# sphericon_v3.net
KiCad netlist of a schematic drawn in EAGLE
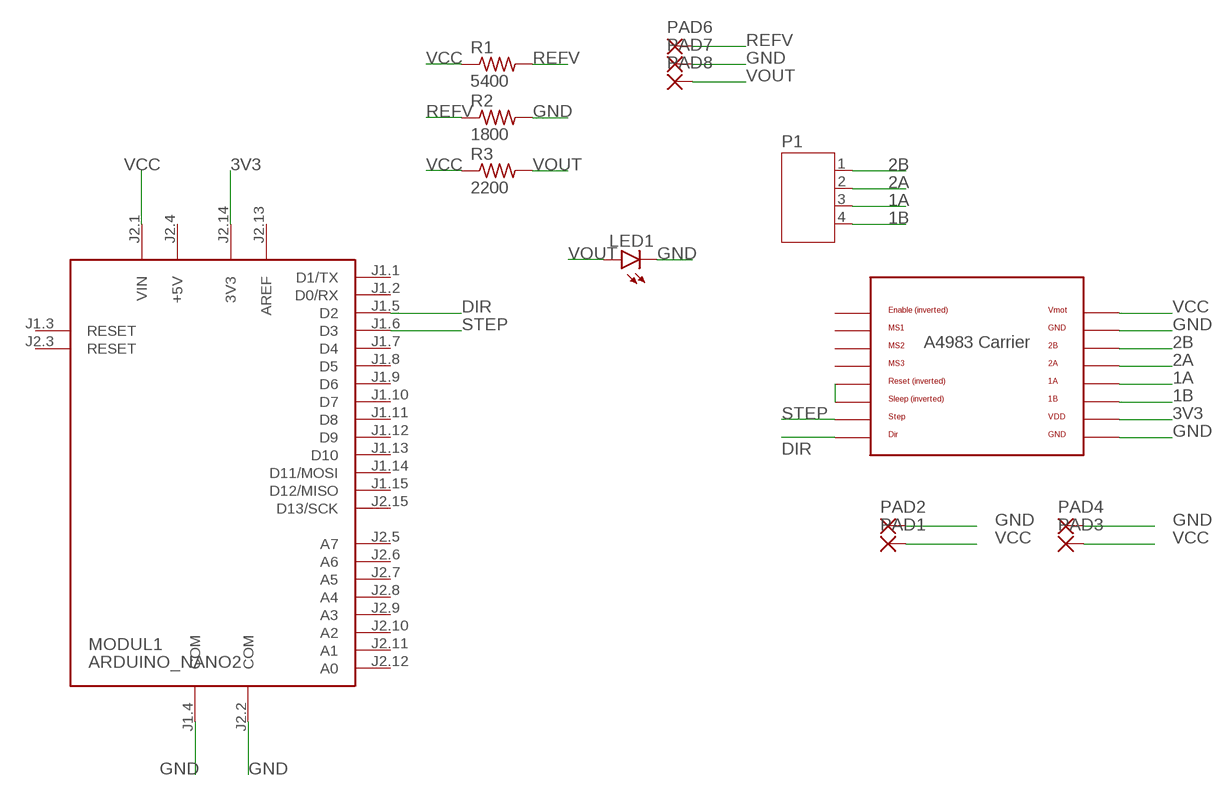
[diagram p0: schematic, sheet 1]

(export (version "E")
  (design (tool "Eeschema 10.0.6"))
  (components
    (comp (ref "LED1")
      (value "LED3MM")
      (footprint "eagle-import:LED3MM")
      (libsource (lib "eagle-import") (part "LED3MM"))
    )
    (comp (ref "MODUL1")
      (value "ARDUINO_NANO2")
      (footprint "eagle-import:ARDUINO_NANO2")
      (libsource (lib "eagle-import") (part "ARDUINO_NANO2"))
    )
    (comp (ref "P1")
      (value "JST-PH4")
      (footprint "eagle-import:JST-PH4")
      (libsource (lib "eagle-import") (part "JST-PH4"))
    )
    (comp (ref "PAD1")
      (value "1,6/0,8")
      (footprint "eagle-import:1,6_0,8")
      (libsource (lib "eagle-import") (part "1,6/0,8"))
    )
    (comp (ref "PAD2")
      (value "1,6/0,8")
      (footprint "eagle-import:1,6_0,8")
      (libsource (lib "eagle-import") (part "1,6/0,8"))
    )
    (comp (ref "PAD3")
      (value "1,6/0,8")
      (footprint "eagle-import:1,6_0,8")
      (libsource (lib "eagle-import") (part "1,6/0,8"))
    )
    (comp (ref "PAD4")
      (value "1,6/0,8")
      (footprint "eagle-import:1,6_0,8")
      (libsource (lib "eagle-import") (part "1,6/0,8"))
    )
    (comp (ref "PAD6")
      (value "1,6/0,8")
      (footprint "eagle-import:1,6_0,8")
      (libsource (lib "eagle-import") (part "1,6/0,8"))
    )
    (comp (ref "PAD7")
      (value "1,6/0,8")
      (footprint "eagle-import:1,6_0,8")
      (libsource (lib "eagle-import") (part "1,6/0,8"))
    )
    (comp (ref "PAD8")
      (value "1,6/0,8")
      (footprint "eagle-import:1,6_0,8")
      (libsource (lib "eagle-import") (part "1,6/0,8"))
    )
    (comp (ref "R1")
      (value "5400")
      (footprint "eagle-import:0204V")
      (libsource (lib "eagle-import") (part "R-US_0204/2V"))
    )
    (comp (ref "R2")
      (value "1800")
      (footprint "eagle-import:0204V")
      (libsource (lib "eagle-import") (part "R-US_0204/2V"))
    )
    (comp (ref "R3")
      (value "2200")
      (footprint "eagle-import:0204V")
      (libsource (lib "eagle-import") (part "R-US_0204/2V"))
    )
    (comp (ref "U$6")
      (value "POLOLU_A4983CARRIER")
      (footprint "eagle-import:A4983CARRIER")
      (libsource (lib "eagle-import") (part "POLOLU_A4983CARRIER"))
    )
  )
  (nets
    (net (code "1") (name "+5V") (class "Default")
      (node (ref "MODUL1") (pin "J2.4") (pinfunction "+5V_J2.4") (pintype "power_in"))
    )
    (net (code "2") (name "1A") (class "Default")
      (node (ref "P1") (pin "3") (pinfunction "3_3") (pintype "passive"))
      (node (ref "U$6") (pin "1A") (pinfunction "1A_1A") (pintype "output"))
    )
    (net (code "3") (name "1B") (class "Default")
      (node (ref "P1") (pin "4") (pinfunction "4_4") (pintype "passive"))
      (node (ref "U$6") (pin "1B") (pinfunction "1B_1B") (pintype "output"))
    )
    (net (code "4") (name "2A") (class "Default")
      (node (ref "P1") (pin "2") (pinfunction "2_2") (pintype "passive"))
      (node (ref "U$6") (pin "2A") (pinfunction "2A_2A") (pintype "output"))
    )
    (net (code "5") (name "2B") (class "Default")
      (node (ref "P1") (pin "1") (pinfunction "1_1") (pintype "passive"))
      (node (ref "U$6") (pin "2B") (pinfunction "2B_2B") (pintype "output"))
    )
    (net (code "6") (name "3V3") (class "Default")
      (node (ref "MODUL1") (pin "J2.14") (pinfunction "3V3_J2.14") (pintype "power_in"))
      (node (ref "U$6") (pin "VDD") (pinfunction "VDD_VDD") (pintype "power_in"))
    )
    (net (code "7") (name "AREF") (class "Default")
      (node (ref "MODUL1") (pin "J2.13") (pinfunction "AREF_J2.13") (pintype "power_in"))
    )
    (net (code "8") (name "DIR") (class "Default")
      (node (ref "MODUL1") (pin "J1.5") (pinfunction "D2_J1.5") (pintype "bidirectional"))
      (node (ref "U$6") (pin "DIR") (pinfunction "DIR_DIR") (pintype "input"))
    )
    (net (code "9") (name "GND") (class "Default")
      (node (ref "LED1") (pin "K") (pinfunction "C_K") (pintype "passive"))
      (node (ref "MODUL1") (pin "J1.4") (pinfunction "COM_J1.4") (pintype "power_in"))
      (node (ref "MODUL1") (pin "J2.2") (pinfunction "COM_J2.2") (pintype "power_in"))
      (node (ref "PAD2") (pin "1") (pinfunction "P_1") (pintype "passive"))
      (node (ref "PAD4") (pin "1") (pinfunction "P_1") (pintype "passive"))
      (node (ref "PAD7") (pin "1") (pinfunction "P_1") (pintype "passive"))
      (node (ref "R2") (pin "2") (pinfunction "2_2") (pintype "passive"))
      (node (ref "U$6") (pin "GND") (pinfunction "GND_GND") (pintype "power_in"))
      (node (ref "U$6") (pin "GND@0") (pinfunction "GND_GND@0") (pintype "power_in"))
    )
    (net (code "10") (name "Net-(U$6-SLEEP)") (class "Default")
      (node (ref "U$6") (pin "RST") (pinfunction "RST_RST") (pintype "input"))
      (node (ref "U$6") (pin "SLP") (pinfunction "SLEEP_SLP") (pintype "input"))
    )
    (net (code "11") (name "REFV") (class "Default")
      (node (ref "PAD6") (pin "1") (pinfunction "P_1") (pintype "passive"))
      (node (ref "R1") (pin "2") (pinfunction "2_2") (pintype "passive"))
      (node (ref "R2") (pin "1") (pinfunction "1_1") (pintype "passive"))
    )
    (net (code "12") (name "STEP") (class "Default")
      (node (ref "MODUL1") (pin "J1.6") (pinfunction "D3_J1.6") (pintype "bidirectional"))
      (node (ref "U$6") (pin "STEP") (pinfunction "STEP_STEP") (pintype "input"))
    )
    (net (code "13") (name "VCC") (class "Default")
      (node (ref "MODUL1") (pin "J2.1") (pinfunction "VIN_J2.1") (pintype "power_in"))
      (node (ref "PAD1") (pin "1") (pinfunction "P_1") (pintype "passive"))
      (node (ref "PAD3") (pin "1") (pinfunction "P_1") (pintype "passive"))
      (node (ref "R1") (pin "1") (pinfunction "1_1") (pintype "passive"))
      (node (ref "R3") (pin "1") (pinfunction "1_1") (pintype "passive"))
      (node (ref "U$6") (pin "VMOT") (pinfunction "VMOT_VMOT") (pintype "power_in"))
    )
    (net (code "14") (name "VOUT") (class "Default")
      (node (ref "LED1") (pin "A") (pinfunction "A_A") (pintype "passive"))
      (node (ref "PAD8") (pin "1") (pinfunction "P_1") (pintype "passive"))
      (node (ref "R3") (pin "2") (pinfunction "2_2") (pintype "passive"))
    )
    (net (code "15") (name "unconnected-(MODUL1-A0-PadJ2.12)") (class "Default")
      (node (ref "MODUL1") (pin "J2.12") (pinfunction "A0_J2.12") (pintype "bidirectional"))
    )
    (net (code "16") (name "unconnected-(MODUL1-A1-PadJ2.11)") (class "Default")
      (node (ref "MODUL1") (pin "J2.11") (pinfunction "A1_J2.11") (pintype "bidirectional"))
    )
    (net (code "17") (name "unconnected-(MODUL1-A2-PadJ2.10)") (class "Default")
      (node (ref "MODUL1") (pin "J2.10") (pinfunction "A2_J2.10") (pintype "bidirectional"))
    )
    (net (code "18") (name "unconnected-(MODUL1-A3-PadJ2.9)") (class "Default")
      (node (ref "MODUL1") (pin "J2.9") (pinfunction "A3_J2.9") (pintype "bidirectional"))
    )
    (net (code "19") (name "unconnected-(MODUL1-A4-PadJ2.8)") (class "Default")
      (node (ref "MODUL1") (pin "J2.8") (pinfunction "A4_J2.8") (pintype "bidirectional"))
    )
    (net (code "20") (name "unconnected-(MODUL1-A5-PadJ2.7)") (class "Default")
      (node (ref "MODUL1") (pin "J2.7") (pinfunction "A5_J2.7") (pintype "bidirectional"))
    )
    (net (code "21") (name "unconnected-(MODUL1-A6-PadJ2.6)") (class "Default")
      (node (ref "MODUL1") (pin "J2.6") (pinfunction "A6_J2.6") (pintype "bidirectional"))
    )
    (net (code "22") (name "unconnected-(MODUL1-A7-PadJ2.5)") (class "Default")
      (node (ref "MODUL1") (pin "J2.5") (pinfunction "A7_J2.5") (pintype "bidirectional"))
    )
    (net (code "23") (name "unconnected-(MODUL1-D0{slash}RX-PadJ1.2)") (class "Default")
      (node (ref "MODUL1") (pin "J1.2") (pinfunction "D0/RX_J1.2") (pintype "bidirectional"))
    )
    (net (code "24") (name "unconnected-(MODUL1-D1{slash}TX-PadJ1.1)") (class "Default")
      (node (ref "MODUL1") (pin "J1.1") (pinfunction "D1/TX_J1.1") (pintype "bidirectional"))
    )
    (net (code "25") (name "unconnected-(MODUL1-D4-PadJ1.7)") (class "Default")
      (node (ref "MODUL1") (pin "J1.7") (pinfunction "D4_J1.7") (pintype "bidirectional"))
    )
    (net (code "26") (name "unconnected-(MODUL1-D5-PadJ1.8)") (class "Default")
      (node (ref "MODUL1") (pin "J1.8") (pinfunction "D5_J1.8") (pintype "bidirectional"))
    )
    (net (code "27") (name "unconnected-(MODUL1-D6-PadJ1.9)") (class "Default")
      (node (ref "MODUL1") (pin "J1.9") (pinfunction "D6_J1.9") (pintype "bidirectional"))
    )
    (net (code "28") (name "unconnected-(MODUL1-D7-PadJ1.10)") (class "Default")
      (node (ref "MODUL1") (pin "J1.10") (pinfunction "D7_J1.10") (pintype "bidirectional"))
    )
    (net (code "29") (name "unconnected-(MODUL1-D8-PadJ1.11)") (class "Default")
      (node (ref "MODUL1") (pin "J1.11") (pinfunction "D8_J1.11") (pintype "bidirectional"))
    )
    (net (code "30") (name "unconnected-(MODUL1-D9-PadJ1.12)") (class "Default")
      (node (ref "MODUL1") (pin "J1.12") (pinfunction "D9_J1.12") (pintype "bidirectional"))
    )
    (net (code "31") (name "unconnected-(MODUL1-D10-PadJ1.13)") (class "Default")
      (node (ref "MODUL1") (pin "J1.13") (pinfunction "D10_J1.13") (pintype "bidirectional"))
    )
    (net (code "32") (name "unconnected-(MODUL1-D11{slash}MOSI-PadJ1.14)") (class "Default")
      (node (ref "MODUL1") (pin "J1.14") (pinfunction "D11/MOSI_J1.14") (pintype "bidirectional"))
    )
    (net (code "33") (name "unconnected-(MODUL1-D12{slash}MISO-PadJ1.15)") (class "Default")
      (node (ref "MODUL1") (pin "J1.15") (pinfunction "D12/MISO_J1.15") (pintype "bidirectional"))
    )
    (net (code "34") (name "unconnected-(MODUL1-D13{slash}SCK-PadJ2.15)") (class "Default")
      (node (ref "MODUL1") (pin "J2.15") (pinfunction "D13/SCK_J2.15") (pintype "bidirectional"))
    )
    (net (code "35") (name "unconnected-(MODUL1-RESET-PadJ1.3)") (class "Default")
      (node (ref "MODUL1") (pin "J1.3") (pinfunction "RESET_J1.3") (pintype "bidirectional"))
    )
    (net (code "36") (name "unconnected-(MODUL1-RESET-PadJ2.3)") (class "Default")
      (node (ref "MODUL1") (pin "J2.3") (pinfunction "RESET_J2.3") (pintype "bidirectional"))
    )
    (net (code "37") (name "unconnected-(U$6-PadEN)") (class "Default")
      (node (ref "U$6") (pin "EN") (pinfunction "EN_EN") (pintype "input"))
    )
    (net (code "38") (name "unconnected-(U$6-PadMS1)") (class "Default")
      (node (ref "U$6") (pin "MS1") (pinfunction "MS1_MS1") (pintype "input"))
    )
    (net (code "39") (name "unconnected-(U$6-PadMS2)") (class "Default")
      (node (ref "U$6") (pin "MS2") (pinfunction "MS2_MS2") (pintype "input"))
    )
    (net (code "40") (name "unconnected-(U$6-PadMS3)") (class "Default")
      (node (ref "U$6") (pin "MS3") (pinfunction "MS3_MS3") (pintype "input"))
    )
  )
)
